# Power.net
KiCad netlist of a schematic drawn in Altium Designer
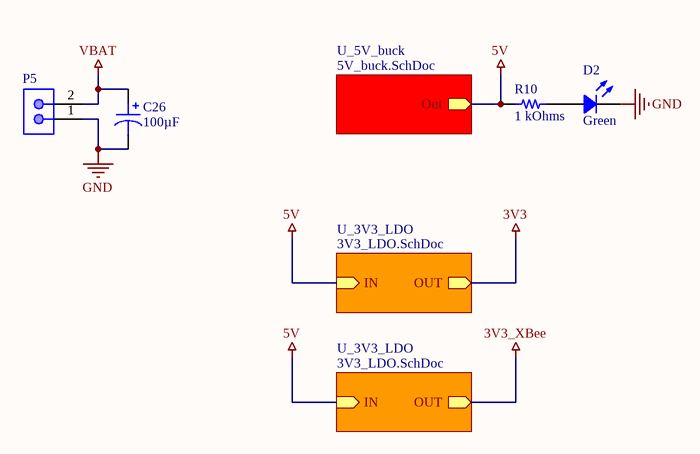
[diagram p0: Power.SchDoc]

(export (version "E")
  (design (tool "Eeschema 10.0.6"))
  (components
    (comp (ref "C26")
      (value "100µF")
      (footprint "CAP POL 2917_7343")
      (description "CAP TANT 100UF 20% 20V 2917")
      (fields (field (name "PART NUMBER") "293D107X0020E2TE3") (field (name "MANUFACTURER") "Vishay Sprague"))
      (libsource (lib "Celestial Altium Library - altium_library") (part "Polarised Capacitor"))
    )
    (comp (ref "D2")
      (value "Green")
      (footprint "LED 0603_1608 GREEN")
      (description "1.6X0.8MM LC GREEN PIXSOLED DOME")
      (fields (field (name "PART NUMBER") "XZCDGK53W-8VF") (field (name "MANUFACTURER") "SunLED"))
      (libsource (lib "Celestial Altium Library - altium_library") (part "LED"))
    )
    (comp (ref "P5")
      (value "2 pin 2mm JST Male")
      (footprint "2pin - 2mm JST male")
      (libsource (lib "IC") (part "2 pin 2mm JST Male"))
    )
    (comp (ref "R10")
      (value "1 kOhms")
      (footprint "RES 0603_1608")
      (description "RES 1K OHM 0.5% 1/10W 0603")
      (fields
        (field (name "PART NUMBER") "RNCF0603DTE1K00")
        (field (name "MANUFACTURER") "Stackpole Electronics Inc")
      )
      (libsource (lib "Celestial Altium Library - altium_library") (part "Resistor"))
    )
  )
  (nets
    (net (code "3") (name "5V") (class "Default")
      (node (ref "R10") (pin "1") (pinfunction "1_1") (pintype "passive"))
    )
    (net (code "4") (name "GND") (class "Default")
      (node (ref "C26") (pin "2") (pinfunction "2_2") (pintype "passive"))
      (node (ref "D2") (pin "2") (pinfunction "2_2") (pintype "passive"))
      (node (ref "P5") (pin "1") (pinfunction "1_1") (pintype "passive"))
    )
    (net (code "5") (name "Net-(D2-Pad1)") (class "Default")
      (node (ref "D2") (pin "1") (pinfunction "1_1") (pintype "passive"))
      (node (ref "R10") (pin "2") (pinfunction "2_2") (pintype "passive"))
    )
    (net (code "6") (name "VBAT") (class "Default")
      (node (ref "C26") (pin "1") (pinfunction "1_1") (pintype "passive"))
      (node (ref "P5") (pin "2") (pinfunction "2_2") (pintype "passive"))
    )
  )
)
